# FOTA.net
KiCad netlist of a schematic drawn in Altium Designer
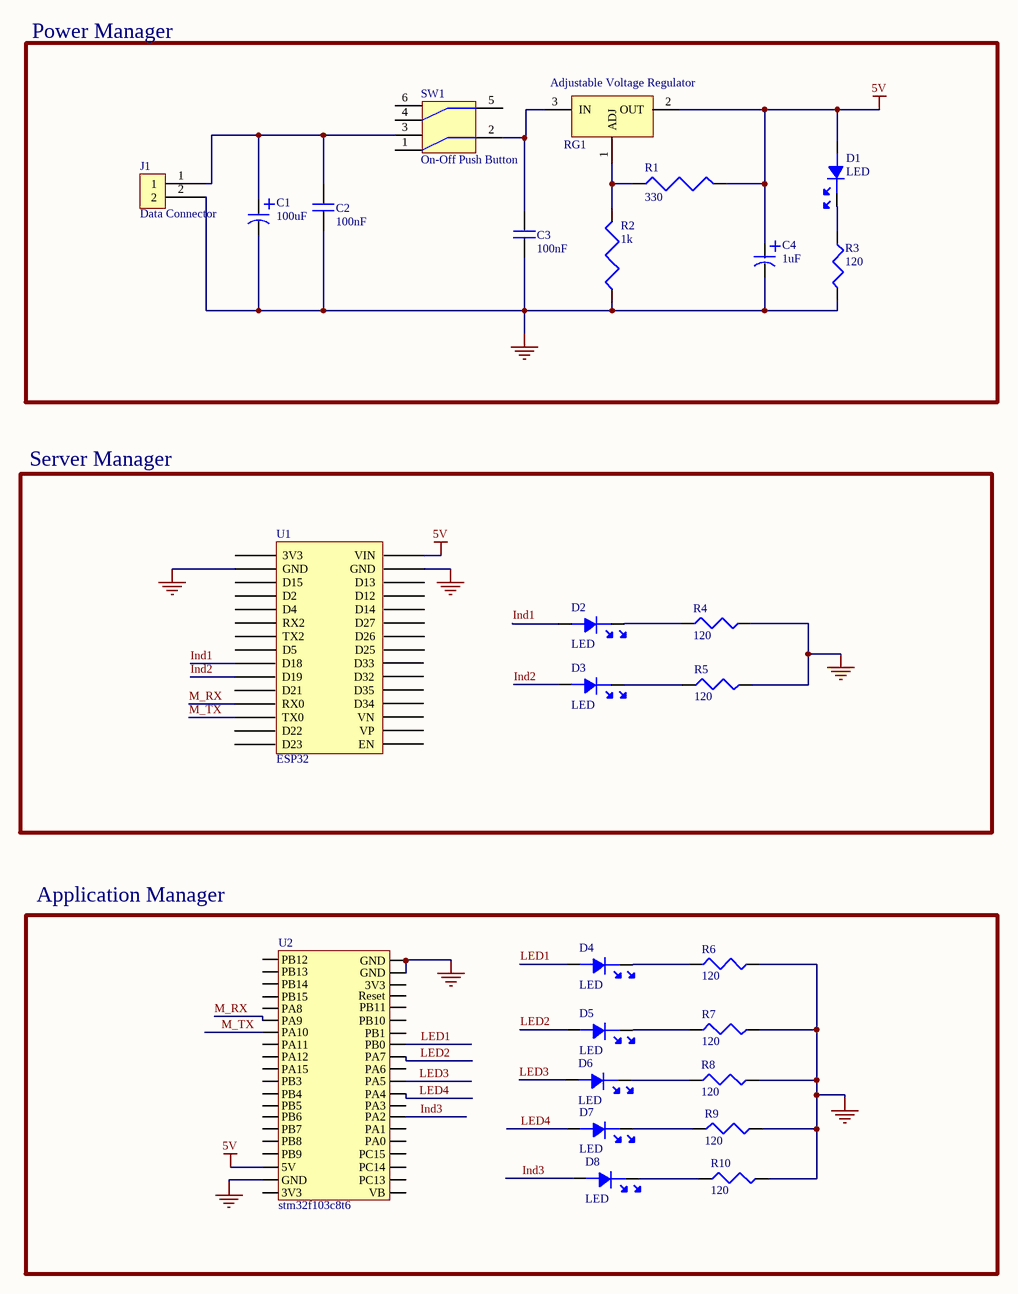
[diagram p0: FOTA.SchDoc]

(export (version "E")
  (design (tool "Eeschema 10.0.6"))
  (components
    (comp (ref "C1")
      (value "100uF")
      (footprint "CapacitorPOL")
      (fields (field (name "TOLERANCE") "20%"))
      (libsource (lib "FOTA") (part "CAP 100u"))
    )
    (comp (ref "C2")
      (value "100nF")
      (footprint "CAP non")
      (description "Generial Non polarized capacitor for through hole or SMD capacitors")
      (libsource (lib "FOTA") (part "Non polarized capacitor"))
    )
    (comp (ref "C3")
      (value "100nF")
      (footprint "CAP non")
      (description "Generial Non polarized capacitor for through hole or SMD capacitors")
      (libsource (lib "FOTA") (part "Non polarized capacitor"))
    )
    (comp (ref "C4")
      (value "1uF")
      (footprint "CapacitorPOL")
      (description "10uF 35 V dc Aluminium Electrolytic Capacitor; BX Series 1000h 10(Dia.)x12.5mm")
      (fields (field (name "TOLERANCE") "20%") (field (name "VOLTAGE") "35V"))
      (libsource (lib "FOTA") (part "CAP 10u"))
    )
    (comp (ref "D1")
      (value "LED")
      (footprint "LED")
      (description "Led, Red, T-1 (3Mm), 630 Nm, 1.8 V, 30 Ma, 20 Mcd Rohs Compliant: Yes")
      (libsource (lib "FOTA") (part "LED"))
    )
    (comp (ref "D2")
      (value "LED")
      (footprint "LED")
      (description "Led, Red, T-1 (3Mm), 630 Nm, 1.8 V, 30 Ma, 20 Mcd Rohs Compliant: Yes")
      (libsource (lib "FOTA") (part "LED"))
    )
    (comp (ref "D3")
      (value "LED")
      (footprint "LED")
      (description "Led, Red, T-1 (3Mm), 630 Nm, 1.8 V, 30 Ma, 20 Mcd Rohs Compliant: Yes")
      (libsource (lib "FOTA") (part "LED"))
    )
    (comp (ref "D4")
      (value "LED")
      (footprint "LED")
      (description "Led, Red, T-1 (3Mm), 630 Nm, 1.8 V, 30 Ma, 20 Mcd Rohs Compliant: Yes")
      (libsource (lib "FOTA") (part "LED"))
    )
    (comp (ref "D5")
      (value "LED")
      (footprint "LED")
      (description "Led, Red, T-1 (3Mm), 630 Nm, 1.8 V, 30 Ma, 20 Mcd Rohs Compliant: Yes")
      (libsource (lib "FOTA") (part "LED"))
    )
    (comp (ref "D6")
      (value "LED")
      (footprint "LED")
      (description "Led, Red, T-1 (3Mm), 630 Nm, 1.8 V, 30 Ma, 20 Mcd Rohs Compliant: Yes")
      (libsource (lib "FOTA") (part "LED"))
    )
    (comp (ref "D7")
      (value "LED")
      (footprint "LED")
      (description "Led, Red, T-1 (3Mm), 630 Nm, 1.8 V, 30 Ma, 20 Mcd Rohs Compliant: Yes")
      (libsource (lib "FOTA") (part "LED"))
    )
    (comp (ref "D8")
      (value "LED")
      (footprint "LED")
      (description "Led, Red, T-1 (3Mm), 630 Nm, 1.8 V, 30 Ma, 20 Mcd Rohs Compliant: Yes")
      (libsource (lib "FOTA") (part "LED"))
    )
    (comp (ref "J1")
      (value "Data Connector")
      (footprint "Data Connnector 2 pins")
      (libsource (lib "FOTA") (part "Data Connector 2 pins"))
    )
    (comp (ref "R1")
      (value "330")
      (footprint "330")
      (description "General Type Carbon Film Resistor 330Ohm 1/4W 5% Axial Bulk")
      (fields (field (name "TOLERANCE") "5%"))
      (libsource (lib "FOTA") (part "R330"))
    )
    (comp (ref "R2")
      (value "1k")
      (footprint "R-1k")
      (description "Res Carbon Film 1K Ohm 5% 1/4W -400ppm/°C to 0ppm/°C Conformal AXL Thru-Hole T/R")
      (fields (field (name "TOLERANCE") "5%"))
      (libsource (lib "FOTA") (part "R 1k"))
    )
    (comp (ref "R3")
      (value "120")
      (footprint "R120")
      (description "General Type Carbon Film Resistor 120Ohm 1/4W 5% Axial Bulk")
      (fields (field (name "TOLERANCE") "5%"))
      (libsource (lib "FOTA") (part "R120"))
    )
    (comp (ref "R4")
      (value "120")
      (footprint "R120")
      (description "General Type Carbon Film Resistor 120Ohm 1/4W 5% Axial Bulk")
      (fields (field (name "TOLERANCE") "5%"))
      (libsource (lib "FOTA") (part "R120"))
    )
    (comp (ref "R5")
      (value "120")
      (footprint "R120")
      (description "General Type Carbon Film Resistor 120Ohm 1/4W 5% Axial Bulk")
      (fields (field (name "TOLERANCE") "5%"))
      (libsource (lib "FOTA") (part "R120"))
    )
    (comp (ref "R6")
      (value "120")
      (footprint "R120")
      (description "General Type Carbon Film Resistor 120Ohm 1/4W 5% Axial Bulk")
      (fields (field (name "TOLERANCE") "5%"))
      (libsource (lib "FOTA") (part "R120"))
    )
    (comp (ref "R7")
      (value "120")
      (footprint "R120")
      (description "General Type Carbon Film Resistor 120Ohm 1/4W 5% Axial Bulk")
      (fields (field (name "TOLERANCE") "5%"))
      (libsource (lib "FOTA") (part "R120"))
    )
    (comp (ref "R8")
      (value "120")
      (footprint "R120")
      (description "General Type Carbon Film Resistor 120Ohm 1/4W 5% Axial Bulk")
      (fields (field (name "TOLERANCE") "5%"))
      (libsource (lib "FOTA") (part "R120"))
    )
    (comp (ref "R9")
      (value "120")
      (footprint "R120")
      (description "General Type Carbon Film Resistor 120Ohm 1/4W 5% Axial Bulk")
      (fields (field (name "TOLERANCE") "5%"))
      (libsource (lib "FOTA") (part "R120"))
    )
    (comp (ref "R10")
      (value "120")
      (footprint "R120")
      (description "General Type Carbon Film Resistor 120Ohm 1/4W 5% Axial Bulk")
      (fields (field (name "TOLERANCE") "5%"))
      (libsource (lib "FOTA") (part "R120"))
    )
    (comp (ref "RG1")
      (value "Adjustable Voltage Regulator")
      (footprint "Regulator")
      (libsource (lib "FOTA") (part "LM350"))
    )
    (comp (ref "SW1")
      (value "On-Off Push Button")
      (footprint "DIP6 - SW")
      (libsource (lib "FOTA") (part "On-Off Push Button"))
    )
    (comp (ref "U1") (value "ESP32") (footprint "ESP32") (libsource (lib "FOTA") (part "ESP32")))
    (comp (ref "U2")
      (value "stm32f103c8t6")
      (footprint "DIP46")
      (description "STM32 Nucleo-32 development board with STM32F031K6 MCU, supports Arduino connectivity")
      (libsource (lib "FOTA") (part "stm32f103c8t6"))
    )
  )
  (nets
    (net (code "1") (name "/Ind1") (class "Default")
      (node (ref "D2") (pin "1") (pinfunction "1_1") (pintype "passive"))
      (node (ref "U1") (pin "9") (pinfunction "D18_9") (pintype "passive"))
    )
    (net (code "2") (name "/Ind2") (class "Default")
      (node (ref "D3") (pin "1") (pinfunction "1_1") (pintype "passive"))
      (node (ref "U1") (pin "10") (pinfunction "D19_10") (pintype "passive"))
    )
    (net (code "3") (name "/Ind3") (class "Default")
      (node (ref "D8") (pin "1") (pinfunction "1_1") (pintype "passive"))
      (node (ref "U2") (pin "7") (pinfunction "PA2_7") (pintype "passive"))
    )
    (net (code "4") (name "/LED1") (class "Default")
      (node (ref "D4") (pin "1") (pinfunction "1_1") (pintype "passive"))
      (node (ref "U2") (pin "13") (pinfunction "PB0_13") (pintype "passive"))
    )
    (net (code "5") (name "/LED2") (class "Default")
      (node (ref "D5") (pin "1") (pinfunction "1_1") (pintype "passive"))
      (node (ref "U2") (pin "12") (pinfunction "PA7_12") (pintype "passive"))
    )
    (net (code "6") (name "/LED3") (class "Default")
      (node (ref "D6") (pin "1") (pinfunction "1_1") (pintype "passive"))
      (node (ref "U2") (pin "10") (pinfunction "PA5_10") (pintype "passive"))
    )
    (net (code "7") (name "/LED4") (class "Default")
      (node (ref "D7") (pin "1") (pinfunction "1_1") (pintype "passive"))
      (node (ref "U2") (pin "9") (pinfunction "PA4_9") (pintype "passive"))
    )
    (net (code "8") (name "/M_RX") (class "Default")
      (node (ref "U1") (pin "12") (pinfunction "RX0_12") (pintype "passive"))
      (node (ref "U2") (pin "32") (pinfunction "PA9_32") (pintype "passive"))
    )
    (net (code "9") (name "/M_TX") (class "Default")
      (node (ref "U1") (pin "13") (pinfunction "TX0_13") (pintype "passive"))
      (node (ref "U2") (pin "33") (pinfunction "PA10_33") (pintype "passive"))
    )
    (net (code "10") (name "5V") (class "Default")
      (node (ref "C4") (pin "1") (pinfunction "3_1") (pintype "passive"))
      (node (ref "D1") (pin "1") (pinfunction "1_1") (pintype "passive"))
      (node (ref "R1") (pin "1") (pinfunction "1_1") (pintype "passive"))
      (node (ref "RG1") (pin "2") (pinfunction "OUT_2") (pintype "passive"))
      (node (ref "U1") (pin "30") (pinfunction "VIN_30") (pintype "passive"))
      (node (ref "U2") (pin "44") (pinfunction "5V_44") (pintype "passive"))
    )
    (net (code "11") (name "GND") (class "Default")
      (node (ref "C1") (pin "2") (pinfunction "2_2") (pintype "passive"))
      (node (ref "C2") (pin "2") (pinfunction "2_2") (pintype "passive"))
      (node (ref "C3") (pin "2") (pinfunction "2_2") (pintype "passive"))
      (node (ref "C4") (pin "2") (pinfunction "2_2") (pintype "passive"))
      (node (ref "J1") (pin "2") (pinfunction "2_2") (pintype "passive"))
      (node (ref "R10") (pin "1") (pinfunction "1_1") (pintype "passive"))
      (node (ref "R2") (pin "2") (pinfunction "2_2") (pintype "passive"))
      (node (ref "R3") (pin "1") (pinfunction "1_1") (pintype "passive"))
      (node (ref "R4") (pin "1") (pinfunction "1_1") (pintype "passive"))
      (node (ref "R5") (pin "1") (pinfunction "1_1") (pintype "passive"))
      (node (ref "R6") (pin "1") (pinfunction "1_1") (pintype "passive"))
      (node (ref "R7") (pin "1") (pinfunction "1_1") (pintype "passive"))
      (node (ref "R8") (pin "1") (pinfunction "1_1") (pintype "passive"))
      (node (ref "R9") (pin "1") (pinfunction "1_1") (pintype "passive"))
      (node (ref "U1") (pin "2") (pinfunction "GND_2") (pintype "passive"))
      (node (ref "U1") (pin "29") (pinfunction "GND_29") (pintype "passive"))
      (node (ref "U2") (pin "19") (pinfunction "GND_19") (pintype "passive"))
      (node (ref "U2") (pin "20") (pinfunction "GND_20") (pintype "passive"))
      (node (ref "U2") (pin "45") (pinfunction "GND_45") (pintype "passive"))
    )
    (net (code "12") (name "Net-(C1-3)") (class "Default")
      (node (ref "C1") (pin "1") (pinfunction "3_1") (pintype "passive"))
      (node (ref "C2") (pin "1") (pinfunction "1_1") (pintype "passive"))
      (node (ref "J1") (pin "1") (pinfunction "1_1") (pintype "passive"))
      (node (ref "SW1") (pin "3") (pinfunction "3_3") (pintype "passive"))
    )
    (net (code "13") (name "Net-(D1-Pad2)") (class "Default")
      (node (ref "D1") (pin "2") (pinfunction "2_2") (pintype "passive"))
      (node (ref "R3") (pin "2") (pinfunction "2_2") (pintype "passive"))
    )
    (net (code "14") (name "Net-(D2-Pad2)") (class "Default")
      (node (ref "D2") (pin "2") (pinfunction "2_2") (pintype "passive"))
      (node (ref "R4") (pin "2") (pinfunction "2_2") (pintype "passive"))
    )
    (net (code "15") (name "Net-(D3-Pad2)") (class "Default")
      (node (ref "D3") (pin "2") (pinfunction "2_2") (pintype "passive"))
      (node (ref "R5") (pin "2") (pinfunction "2_2") (pintype "passive"))
    )
    (net (code "16") (name "Net-(D4-Pad2)") (class "Default")
      (node (ref "D4") (pin "2") (pinfunction "2_2") (pintype "passive"))
      (node (ref "R6") (pin "2") (pinfunction "2_2") (pintype "passive"))
    )
    (net (code "17") (name "Net-(D5-Pad2)") (class "Default")
      (node (ref "D5") (pin "2") (pinfunction "2_2") (pintype "passive"))
      (node (ref "R7") (pin "2") (pinfunction "2_2") (pintype "passive"))
    )
    (net (code "18") (name "Net-(D6-Pad2)") (class "Default")
      (node (ref "D6") (pin "2") (pinfunction "2_2") (pintype "passive"))
      (node (ref "R8") (pin "2") (pinfunction "2_2") (pintype "passive"))
    )
    (net (code "19") (name "Net-(D7-Pad2)") (class "Default")
      (node (ref "D7") (pin "2") (pinfunction "2_2") (pintype "passive"))
      (node (ref "R9") (pin "2") (pinfunction "2_2") (pintype "passive"))
    )
    (net (code "20") (name "Net-(D8-Pad2)") (class "Default")
      (node (ref "D8") (pin "2") (pinfunction "2_2") (pintype "passive"))
      (node (ref "R10") (pin "2") (pinfunction "2_2") (pintype "passive"))
    )
    (net (code "21") (name "Net-(RG1-ADJ)") (class "Default")
      (node (ref "R1") (pin "2") (pinfunction "2_2") (pintype "passive"))
      (node (ref "R2") (pin "1") (pinfunction "1_1") (pintype "passive"))
      (node (ref "RG1") (pin "1") (pinfunction "ADJ_1") (pintype "passive"))
    )
    (net (code "22") (name "Net-(RG1-IN)") (class "Default")
      (node (ref "C3") (pin "1") (pinfunction "1_1") (pintype "passive"))
      (node (ref "RG1") (pin "3") (pinfunction "IN_3") (pintype "passive"))
      (node (ref "SW1") (pin "2") (pinfunction "2_2") (pintype "passive"))
    )
    (net (code "23") (name "unconnected-(SW1-Pad1)") (class "Default")
      (node (ref "SW1") (pin "1") (pinfunction "1_1") (pintype "passive"))
    )
    (net (code "24") (name "unconnected-(SW1-Pad4)") (class "Default")
      (node (ref "SW1") (pin "4") (pinfunction "4_4") (pintype "passive"))
    )
    (net (code "25") (name "unconnected-(SW1-Pad5)") (class "Default")
      (node (ref "SW1") (pin "5") (pinfunction "5_5") (pintype "passive"))
    )
    (net (code "26") (name "unconnected-(SW1-Pad6)") (class "Default")
      (node (ref "SW1") (pin "6") (pinfunction "6_6") (pintype "passive"))
    )
    (net (code "27") (name "unconnected-(U1-3V3-Pad1)") (class "Default")
      (node (ref "U1") (pin "1") (pinfunction "3V3_1") (pintype "passive"))
    )
    (net (code "28") (name "unconnected-(U1-D2-Pad4)") (class "Default")
      (node (ref "U1") (pin "4") (pinfunction "D2_4") (pintype "passive"))
    )
    (net (code "29") (name "unconnected-(U1-D4-Pad5)") (class "Default")
      (node (ref "U1") (pin "5") (pinfunction "D4_5") (pintype "passive"))
    )
    (net (code "30") (name "unconnected-(U1-D5-Pad8)") (class "Default")
      (node (ref "U1") (pin "8") (pinfunction "D5_8") (pintype "passive"))
    )
    (net (code "31") (name "unconnected-(U1-D12-Pad27)") (class "Default")
      (node (ref "U1") (pin "27") (pinfunction "D12_27") (pintype "passive"))
    )
    (net (code "32") (name "unconnected-(U1-D13-Pad28)") (class "Default")
      (node (ref "U1") (pin "28") (pinfunction "D13_28") (pintype "passive"))
    )
    (net (code "33") (name "unconnected-(U1-D14-Pad26)") (class "Default")
      (node (ref "U1") (pin "26") (pinfunction "D14_26") (pintype "passive"))
    )
    (net (code "34") (name "unconnected-(U1-D15-Pad3)") (class "Default")
      (node (ref "U1") (pin "3") (pinfunction "D15_3") (pintype "passive"))
    )
    (net (code "35") (name "unconnected-(U1-D21-Pad11)") (class "Default")
      (node (ref "U1") (pin "11") (pinfunction "D21_11") (pintype "passive"))
    )
    (net (code "36") (name "unconnected-(U1-D22-Pad14)") (class "Default")
      (node (ref "U1") (pin "14") (pinfunction "D22_14") (pintype "passive"))
    )
    (net (code "37") (name "unconnected-(U1-D23-Pad15)") (class "Default")
      (node (ref "U1") (pin "15") (pinfunction "D23_15") (pintype "passive"))
    )
    (net (code "38") (name "unconnected-(U1-D25-Pad23)") (class "Default")
      (node (ref "U1") (pin "23") (pinfunction "D25_23") (pintype "passive"))
    )
    (net (code "39") (name "unconnected-(U1-D26-Pad24)") (class "Default")
      (node (ref "U1") (pin "24") (pinfunction "D26_24") (pintype "passive"))
    )
    (net (code "40") (name "unconnected-(U1-D27-Pad25)") (class "Default")
      (node (ref "U1") (pin "25") (pinfunction "D27_25") (pintype "passive"))
    )
    (net (code "41") (name "unconnected-(U1-D32-Pad21)") (class "Default")
      (node (ref "U1") (pin "21") (pinfunction "D32_21") (pintype "passive"))
    )
    (net (code "42") (name "unconnected-(U1-D33-Pad22)") (class "Default")
      (node (ref "U1") (pin "22") (pinfunction "D33_22") (pintype "passive"))
    )
    (net (code "43") (name "unconnected-(U1-D34-Pad19)") (class "Default")
      (node (ref "U1") (pin "19") (pinfunction "D34_19") (pintype "passive"))
    )
    (net (code "44") (name "unconnected-(U1-D35-Pad20)") (class "Default")
      (node (ref "U1") (pin "20") (pinfunction "D35_20") (pintype "passive"))
    )
    (net (code "45") (name "unconnected-(U1-EN-Pad16)") (class "Default")
      (node (ref "U1") (pin "16") (pinfunction "EN_16") (pintype "passive"))
    )
    (net (code "46") (name "unconnected-(U1-RX2-Pad6)") (class "Default")
      (node (ref "U1") (pin "6") (pinfunction "RX2_6") (pintype "passive"))
    )
    (net (code "47") (name "unconnected-(U1-TX2-Pad7)") (class "Default")
      (node (ref "U1") (pin "7") (pinfunction "TX2_7") (pintype "passive"))
    )
    (net (code "48") (name "unconnected-(U1-VN-Pad18)") (class "Default")
      (node (ref "U1") (pin "18") (pinfunction "VN_18") (pintype "passive"))
    )
    (net (code "49") (name "unconnected-(U1-VP-Pad17)") (class "Default")
      (node (ref "U1") (pin "17") (pinfunction "VP_17") (pintype "passive"))
    )
    (net (code "50") (name "unconnected-(U2-3V3-Pad18)") (class "Default")
      (node (ref "U2") (pin "18") (pinfunction "3V3_18") (pintype "passive"))
    )
    (net (code "51") (name "unconnected-(U2-3V3-Pad46)") (class "Default")
      (node (ref "U2") (pin "46") (pinfunction "3V3_46") (pintype "passive"))
    )
    (net (code "52") (name "unconnected-(U2-PA0-Pad5)") (class "Default")
      (node (ref "U2") (pin "5") (pinfunction "PA0_5") (pintype "passive"))
    )
    (net (code "53") (name "unconnected-(U2-PA1-Pad6)") (class "Default")
      (node (ref "U2") (pin "6") (pinfunction "PA1_6") (pintype "passive"))
    )
    (net (code "54") (name "unconnected-(U2-PA3-Pad8)") (class "Default")
      (node (ref "U2") (pin "8") (pinfunction "PA3_8") (pintype "passive"))
    )
    (net (code "55") (name "unconnected-(U2-PA6-Pad11)") (class "Default")
      (node (ref "U2") (pin "11") (pinfunction "PA6_11") (pintype "passive"))
    )
    (net (code "56") (name "unconnected-(U2-PA8-Pad31)") (class "Default")
      (node (ref "U2") (pin "31") (pinfunction "PA8_31") (pintype "passive"))
    )
    (net (code "57") (name "unconnected-(U2-PA11-Pad34)") (class "Default")
      (node (ref "U2") (pin "34") (pinfunction "PA11_34") (pintype "passive"))
    )
    (net (code "58") (name "unconnected-(U2-PA12-Pad35)") (class "Default")
      (node (ref "U2") (pin "35") (pinfunction "PA12_35") (pintype "passive"))
    )
    (net (code "59") (name "unconnected-(U2-PA15-Pad36)") (class "Default")
      (node (ref "U2") (pin "36") (pinfunction "PA15_36") (pintype "passive"))
    )
    (net (code "60") (name "unconnected-(U2-PB1-Pad14)") (class "Default")
      (node (ref "U2") (pin "14") (pinfunction "PB1_14") (pintype "passive"))
    )
    (net (code "61") (name "unconnected-(U2-PB3-Pad37)") (class "Default")
      (node (ref "U2") (pin "37") (pinfunction "PB3_37") (pintype "passive"))
    )
    (net (code "62") (name "unconnected-(U2-PB4-Pad38)") (class "Default")
      (node (ref "U2") (pin "38") (pinfunction "PB4_38") (pintype "passive"))
    )
    (net (code "63") (name "unconnected-(U2-PB5-Pad39)") (class "Default")
      (node (ref "U2") (pin "39") (pinfunction "PB5_39") (pintype "passive"))
    )
    (net (code "64") (name "unconnected-(U2-PB6-Pad40)") (class "Default")
      (node (ref "U2") (pin "40") (pinfunction "PB6_40") (pintype "passive"))
    )
    (net (code "65") (name "unconnected-(U2-PB7-Pad41)") (class "Default")
      (node (ref "U2") (pin "41") (pinfunction "PB7_41") (pintype "passive"))
    )
    (net (code "66") (name "unconnected-(U2-PB8-Pad42)") (class "Default")
      (node (ref "U2") (pin "42") (pinfunction "PB8_42") (pintype "passive"))
    )
    (net (code "67") (name "unconnected-(U2-PB9-Pad43)") (class "Default")
      (node (ref "U2") (pin "43") (pinfunction "PB9_43") (pintype "passive"))
    )
    (net (code "68") (name "unconnected-(U2-PB10-Pad15)") (class "Default")
      (node (ref "U2") (pin "15") (pinfunction "PB10_15") (pintype "passive"))
    )
    (net (code "69") (name "unconnected-(U2-PB11-Pad16)") (class "Default")
      (node (ref "U2") (pin "16") (pinfunction "PB11_16") (pintype "passive"))
    )
    (net (code "70") (name "unconnected-(U2-PB12-Pad27)") (class "Default")
      (node (ref "U2") (pin "27") (pinfunction "PB12_27") (pintype "passive"))
    )
    (net (code "71") (name "unconnected-(U2-PB13-Pad28)") (class "Default")
      (node (ref "U2") (pin "28") (pinfunction "PB13_28") (pintype "passive"))
    )
    (net (code "72") (name "unconnected-(U2-PB14-Pad29)") (class "Default")
      (node (ref "U2") (pin "29") (pinfunction "PB14_29") (pintype "passive"))
    )
    (net (code "73") (name "unconnected-(U2-PB15-Pad30)") (class "Default")
      (node (ref "U2") (pin "30") (pinfunction "PB15_30") (pintype "passive"))
    )
    (net (code "74") (name "unconnected-(U2-PC13-Pad2)") (class "Default")
      (node (ref "U2") (pin "2") (pinfunction "PC13_2") (pintype "passive"))
    )
    (net (code "75") (name "unconnected-(U2-PC14-Pad3)") (class "Default")
      (node (ref "U2") (pin "3") (pinfunction "PC14_3") (pintype "passive"))
    )
    (net (code "76") (name "unconnected-(U2-PC15-Pad4)") (class "Default")
      (node (ref "U2") (pin "4") (pinfunction "PC15_4") (pintype "passive"))
    )
    (net (code "77") (name "unconnected-(U2-Reset-Pad17)") (class "Default")
      (node (ref "U2") (pin "17") (pinfunction "Reset_17") (pintype "passive"))
    )
    (net (code "78") (name "unconnected-(U2-VB-Pad1)") (class "Default")
      (node (ref "U2") (pin "1") (pinfunction "VB_1") (pintype "passive"))
    )
  )
)
